# Camera_Module.net
KiCad netlist of a schematic drawn in Altium Designer
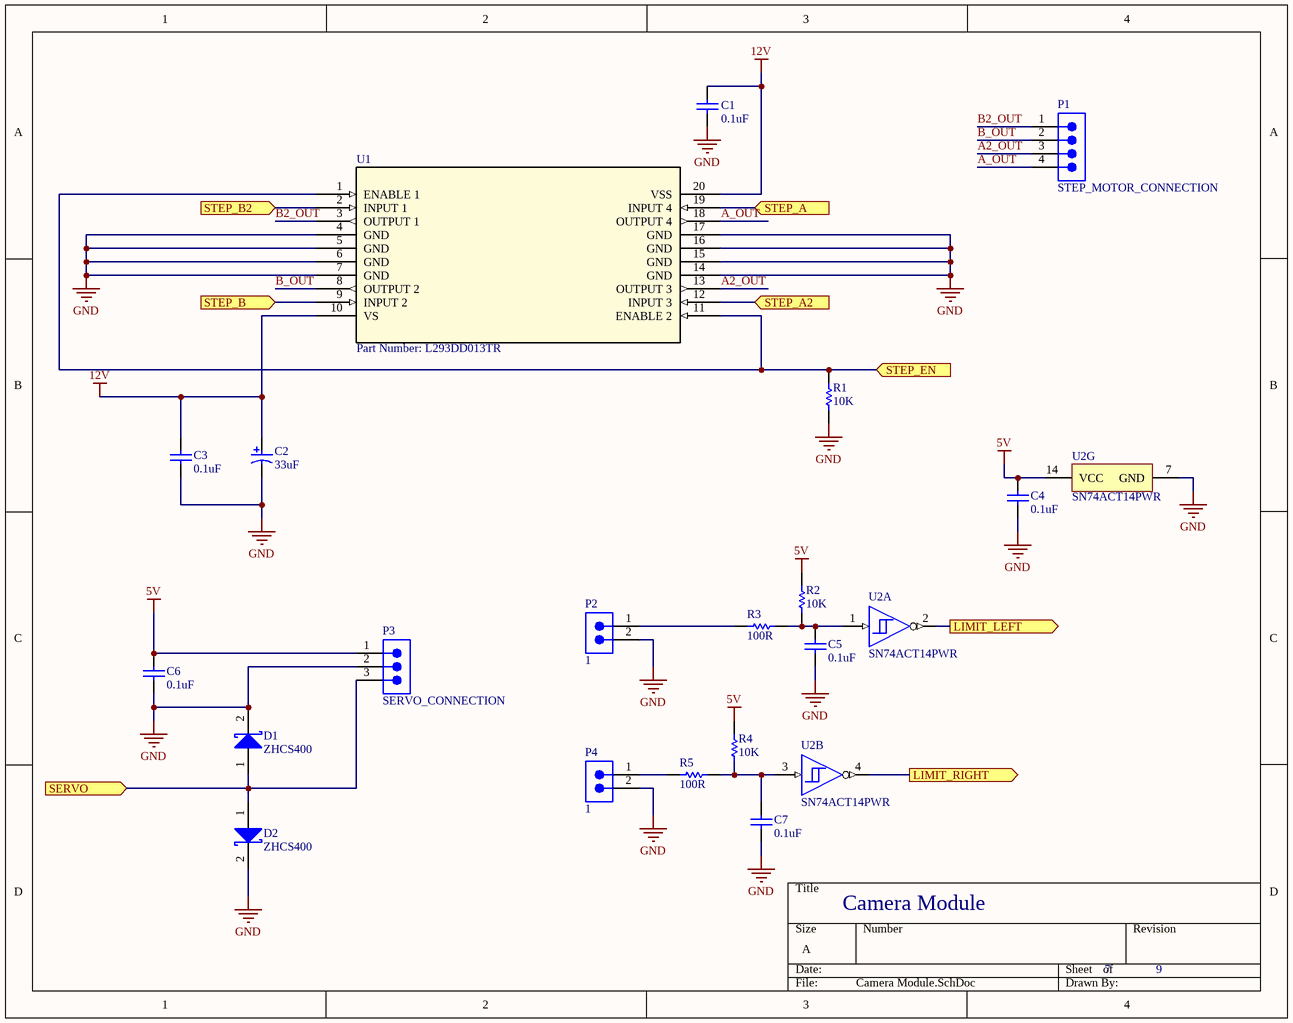
[diagram p0: Camera Module.SchDoc]

(export (version "E")
  (design (tool "Eeschema 10.0.6"))
  (components
    (comp (ref "C1")
      (value "0.1uF")
      (footprint "CAPC1608X90X35LL15T15")
      (description "Chip Capacitor, 100 nF, +/- 10%, 50 V, -55 to 125 degC, 0603 (1608 Metric), RoHS, Tape and Reel")
      (fields (field (name "TOLERANCE") "10%"))
      (libsource (lib "Altium Content Vault") (part "CAP-NP-2"))
    )
    (comp (ref "C2")
      (value "33uF")
      (footprint "NIC-CAPA2-6.3X7.7_V")
      (fields (field (name "PARTNUMBER") "UUD1H330MCL1GS") (field (name "MANUFACTURER") "Nichicon"))
      (libsource (lib "Altium Content Vault") (part "NIC-CAP-P-2"))
    )
    (comp (ref "C3")
      (value "0.1uF")
      (footprint "CAPC1608X90X35LL15T15")
      (description "Chip Capacitor, 100 nF, +/- 10%, 50 V, -55 to 125 degC, 0603 (1608 Metric), RoHS, Tape and Reel")
      (fields (field (name "TOLERANCE") "10%"))
      (libsource (lib "Altium Content Vault") (part "CAP-NP-2"))
    )
    (comp (ref "C4")
      (value "0.1uF")
      (footprint "CAPC1608X90X35LL15T15")
      (description "Chip Capacitor, 100 nF, +/- 10%, 50 V, -55 to 125 degC, 0603 (1608 Metric), RoHS, Tape and Reel")
      (fields (field (name "TOLERANCE") "10%"))
      (libsource (lib "Altium Content Vault") (part "CAP-NP-2"))
    )
    (comp (ref "C5")
      (value "0.1uF")
      (footprint "CAPC1608X90X35LL15T15")
      (description "Chip Capacitor, 100 nF, +/- 10%, 50 V, -55 to 125 degC, 0603 (1608 Metric), RoHS, Tape and Reel")
      (fields (field (name "TOLERANCE") "10%"))
      (libsource (lib "Altium Content Vault") (part "CAP-NP-2"))
    )
    (comp (ref "C6")
      (value "0.1uF")
      (footprint "CAPC1608X90X35LL15T15")
      (description "Chip Capacitor, 100 nF, +/- 10%, 50 V, -55 to 125 degC, 0603 (1608 Metric), RoHS, Tape and Reel")
      (fields (field (name "TOLERANCE") "10%"))
      (libsource (lib "Altium Content Vault") (part "CAP-NP-2"))
    )
    (comp (ref "C7")
      (value "0.1uF")
      (footprint "CAPC1608X90X35LL15T15")
      (description "Chip Capacitor, 100 nF, +/- 10%, 50 V, -55 to 125 degC, 0603 (1608 Metric), RoHS, Tape and Reel")
      (fields (field (name "TOLERANCE") "10%"))
      (libsource (lib "Altium Content Vault") (part "CAP-NP-2"))
    )
    (comp (ref "D1")
      (value "ZHCS400")
      (footprint "DIOD-SOD323-2_V")
      (description "Schottky Diode, 400mA")
      (fields (field (name "MANUFACTURER") "Diodes Inc"))
      (libsource (lib "Altium Content Vault") (part "DIOD-DSKY-A1K2-2"))
    )
    (comp (ref "D2")
      (value "ZHCS400")
      (footprint "DIOD-SOD323-2_V")
      (description "Schottky Diode, 400mA")
      (fields (field (name "MANUFACTURER") "Diodes Inc"))
      (libsource (lib "Altium Content Vault") (part "DIOD-DSKY-A1K2-2"))
    )
    (comp (ref "P1")
      (value "STEP_MOTOR_CONNECTION")
      (footprint "SMTC-TSW-104-08-X-S")
      (description "0.025\" SQ Post Header, Through-hole, Vertical, -55 to 125 degC, 2.54 mm Pitch, 4-Pin, Male, RoHS")
      (fields (field (name "PARTNUMBER") "TSW-104-08-L-S") (field (name "MANUFACTURER") "Samtec"))
      (libsource (lib "Altium Content Vault") (part "SMTC-TSW-104-08-X-S"))
    )
    (comp (ref "P2")
      (value "1")
      (footprint "SMTC-DW-02-16-X-S-200")
      (fields (field (name "PARTNUMBER") "DW-02-16-G-S-200") (field (name "MANUFACTURER") "Samtec"))
      (libsource (lib "Altium Content Vault") (part "SMTC-DW-02-16-X-S-200"))
    )
    (comp (ref "P3")
      (value "SERVO_CONNECTION")
      (footprint "SMTC-TSW-103-07-X-S")
      (description "0.025\" SQ Post Header, Through-hole, Vertical, -55 to 125 degC, 2.54 mm Pitch, 3-Pin, Male, RoHS")
      (fields (field (name "MANUFACTURER") "Samtec") (field (name "PARTNUMBER") "TSW-103-07-L-S"))
      (libsource (lib "Altium Content Vault") (part "SMTC-TSW-103-X-X-S-X"))
    )
    (comp (ref "P4")
      (value "1")
      (footprint "SMTC-DW-02-16-X-S-200")
      (fields (field (name "PARTNUMBER") "DW-02-16-G-S-200") (field (name "MANUFACTURER") "Samtec"))
      (libsource (lib "Altium Content Vault") (part "SMTC-DW-02-16-X-S-200"))
    )
    (comp (ref "R1")
      (value "10K")
      (footprint "RESC1609X50X30ML10T20")
      (fields (field (name "MANUFACTURER") "Vishay Dale") (field (name "PART NUMBER") "CRCW060310K0JNEA"))
      (libsource (lib "Altium Content Vault") (part "RES"))
    )
    (comp (ref "R2")
      (value "10K")
      (footprint "RESC1609X50X30ML10T20")
      (fields (field (name "MANUFACTURER") "Vishay Dale") (field (name "PART NUMBER") "CRCW060310K0JNEA"))
      (libsource (lib "Altium Content Vault") (part "RES"))
    )
    (comp (ref "R3")
      (value "100R")
      (footprint "RESC1609X50X30ML10T20")
      (fields (field (name "PART NUMBER") "CRCW0603100RJNEA") (field (name "MANUFACTURER") "Vishay Dale"))
      (libsource (lib "Altium Content Vault") (part "RES"))
    )
    (comp (ref "R4")
      (value "10K")
      (footprint "RESC1609X50X30ML10T20")
      (fields (field (name "MANUFACTURER") "Vishay Dale") (field (name "PART NUMBER") "CRCW060310K0JNEA"))
      (libsource (lib "Altium Content Vault") (part "RES"))
    )
    (comp (ref "R5")
      (value "100R")
      (footprint "RESC1609X50X30ML10T20")
      (fields (field (name "PART NUMBER") "CRCW0603100RJNEA") (field (name "MANUFACTURER") "Vishay Dale"))
      (libsource (lib "Altium Content Vault") (part "RES"))
    )
    (comp (ref "U1")
      (value "Part Number: L293DD013TR")
      (footprint "SO-20")
      (description "No Description Available")
      (fields
        (field (name "MANUFACTURER_PART_NUMBER") "L293DD013TR")
        (field (name "COPYRIGHT") "Copyright (C) 2018 Accelerated Designs. All rights reserved")
      )
      (libsource (lib "L293") (part "L293DD013TR"))
    )
    (comp (ref "U2")
      (value "SN74ACT14PWR")
      (footprint "PW0014A_N")
      (description "Hex Schmitt-Trigger Inverters, PW0014A, LARGE T&R")
      (fields
        (field (name "GENERIC PART NUMBER") "SN74ACT14")
        (field (name "MANUFACTURER") "Texas Instruments")
      )
      (libsource (lib "Altium Content Vault") (part "TI-CD_SNX4XXXXXX4X_19A-14-SCHMITT"))
    )
  )
  (nets
    (net (code "1") (name "/A2_OUT") (class "Default")
      (node (ref "P1") (pin "3") (pinfunction "3_3") (pintype "passive"))
      (node (ref "U1") (pin "13") (pinfunction "OUTPUT_3_13") (pintype "output"))
    )
    (net (code "2") (name "/A_OUT") (class "Default")
      (node (ref "P1") (pin "4") (pinfunction "4_4") (pintype "passive"))
      (node (ref "U1") (pin "18") (pinfunction "OUTPUT_4_18") (pintype "output"))
    )
    (net (code "3") (name "/B2_OUT") (class "Default")
      (node (ref "P1") (pin "1") (pinfunction "1_1") (pintype "passive"))
      (node (ref "U1") (pin "3") (pinfunction "OUTPUT_1_3") (pintype "output"))
    )
    (net (code "4") (name "/B_OUT") (class "Default")
      (node (ref "P1") (pin "2") (pinfunction "2_2") (pintype "passive"))
      (node (ref "U1") (pin "8") (pinfunction "OUTPUT_2_8") (pintype "output"))
    )
    (net (code "5") (name "/LIMIT_LEFT") (class "Default")
      (node (ref "U2") (pin "2") (pinfunction "~{1Y}_2") (pintype "output"))
    )
    (net (code "6") (name "/LIMIT_RIGHT") (class "Default")
      (node (ref "U2") (pin "4") (pinfunction "~{2Y}_4") (pintype "output"))
    )
    (net (code "7") (name "/SERVO") (class "Default")
      (node (ref "D1") (pin "1") (pinfunction "A_1") (pintype "passive"))
      (node (ref "D2") (pin "1") (pinfunction "A_1") (pintype "passive"))
      (node (ref "P3") (pin "3") (pinfunction "Signal_3") (pintype "passive"))
    )
    (net (code "8") (name "/STEP_A") (class "Default")
      (node (ref "U1") (pin "19") (pinfunction "INPUT_4_19") (pintype "input"))
    )
    (net (code "9") (name "/STEP_A2") (class "Default")
      (node (ref "U1") (pin "12") (pinfunction "INPUT_3_12") (pintype "input"))
    )
    (net (code "10") (name "/STEP_B") (class "Default")
      (node (ref "U1") (pin "9") (pinfunction "INPUT_2_9") (pintype "input"))
    )
    (net (code "11") (name "/STEP_B2") (class "Default")
      (node (ref "U1") (pin "2") (pinfunction "INPUT_1_2") (pintype "input"))
    )
    (net (code "12") (name "/STEP_EN") (class "Default")
      (node (ref "R1") (pin "2") (pinfunction "2_2") (pintype "passive"))
      (node (ref "U1") (pin "1") (pinfunction "ENABLE_1_1") (pintype "input"))
      (node (ref "U1") (pin "11") (pinfunction "ENABLE_2_11") (pintype "input"))
    )
    (net (code "13") (name "5V") (class "Default")
      (node (ref "C4") (pin "2") (pinfunction "2_2") (pintype "passive"))
      (node (ref "C6") (pin "2") (pinfunction "2_2") (pintype "passive"))
      (node (ref "P3") (pin "1") (pinfunction "5V_1") (pintype "passive"))
      (node (ref "R2") (pin "1") (pinfunction "1_1") (pintype "passive"))
      (node (ref "R4") (pin "1") (pinfunction "1_1") (pintype "passive"))
      (node (ref "U2") (pin "14") (pinfunction "VCC_14") (pintype "power_in"))
    )
    (net (code "14") (name "12V") (class "Default")
      (node (ref "C1") (pin "2") (pinfunction "2_2") (pintype "passive"))
      (node (ref "C2") (pin "1") (pinfunction "1_1") (pintype "passive"))
      (node (ref "C3") (pin "2") (pinfunction "2_2") (pintype "passive"))
      (node (ref "U1") (pin "10") (pinfunction "VS_10") (pintype "passive"))
      (node (ref "U1") (pin "20") (pinfunction "VSS_20") (pintype "passive"))
    )
    (net (code "15") (name "GND") (class "Default")
      (node (ref "C1") (pin "1") (pinfunction "1_1") (pintype "passive"))
      (node (ref "C2") (pin "2") (pinfunction "2_2") (pintype "passive"))
      (node (ref "C3") (pin "1") (pinfunction "1_1") (pintype "passive"))
      (node (ref "C4") (pin "1") (pinfunction "1_1") (pintype "passive"))
      (node (ref "C5") (pin "1") (pinfunction "1_1") (pintype "passive"))
      (node (ref "C6") (pin "1") (pinfunction "1_1") (pintype "passive"))
      (node (ref "C7") (pin "1") (pinfunction "1_1") (pintype "passive"))
      (node (ref "D1") (pin "2") (pinfunction "K_2") (pintype "passive"))
      (node (ref "D2") (pin "2") (pinfunction "K_2") (pintype "passive"))
      (node (ref "P2") (pin "2") (pinfunction "2_2") (pintype "passive"))
      (node (ref "P3") (pin "2") (pinfunction "Ground_2") (pintype "passive"))
      (node (ref "P4") (pin "2") (pinfunction "2_2") (pintype "passive"))
      (node (ref "R1") (pin "1") (pinfunction "1_1") (pintype "passive"))
      (node (ref "U1") (pin "14") (pinfunction "GND_14") (pintype "passive"))
      (node (ref "U1") (pin "15") (pinfunction "GND_15") (pintype "passive"))
      (node (ref "U1") (pin "16") (pinfunction "GND_16") (pintype "passive"))
      (node (ref "U1") (pin "17") (pinfunction "GND_17") (pintype "passive"))
      (node (ref "U1") (pin "4") (pinfunction "GND_4") (pintype "passive"))
      (node (ref "U1") (pin "5") (pinfunction "GND_5") (pintype "passive"))
      (node (ref "U1") (pin "6") (pinfunction "GND_6") (pintype "passive"))
      (node (ref "U1") (pin "7") (pinfunction "GND_7") (pintype "passive"))
      (node (ref "U2") (pin "7") (pinfunction "GND_7") (pintype "power_in"))
    )
    (net (code "16") (name "Net-(P2-Pad1)") (class "Default")
      (node (ref "P2") (pin "1") (pinfunction "1_1") (pintype "passive"))
      (node (ref "R3") (pin "1") (pinfunction "1_1") (pintype "passive"))
    )
    (net (code "17") (name "Net-(P4-Pad1)") (class "Default")
      (node (ref "P4") (pin "1") (pinfunction "1_1") (pintype "passive"))
      (node (ref "R5") (pin "1") (pinfunction "1_1") (pintype "passive"))
    )
    (net (code "18") (name "Net-(U2A-1A)") (class "Default")
      (node (ref "C5") (pin "2") (pinfunction "2_2") (pintype "passive"))
      (node (ref "R2") (pin "2") (pinfunction "2_2") (pintype "passive"))
      (node (ref "R3") (pin "2") (pinfunction "2_2") (pintype "passive"))
      (node (ref "U2") (pin "1") (pinfunction "1A_1") (pintype "input"))
    )
    (net (code "19") (name "Net-(U2B-2A)") (class "Default")
      (node (ref "C7") (pin "2") (pinfunction "2_2") (pintype "passive"))
      (node (ref "R4") (pin "2") (pinfunction "2_2") (pintype "passive"))
      (node (ref "R5") (pin "2") (pinfunction "2_2") (pintype "passive"))
      (node (ref "U2") (pin "3") (pinfunction "2A_3") (pintype "input"))
    )
  )
)
